# KMO_IO_MV6.net
KiCad netlist of a schematic drawn in EAGLE
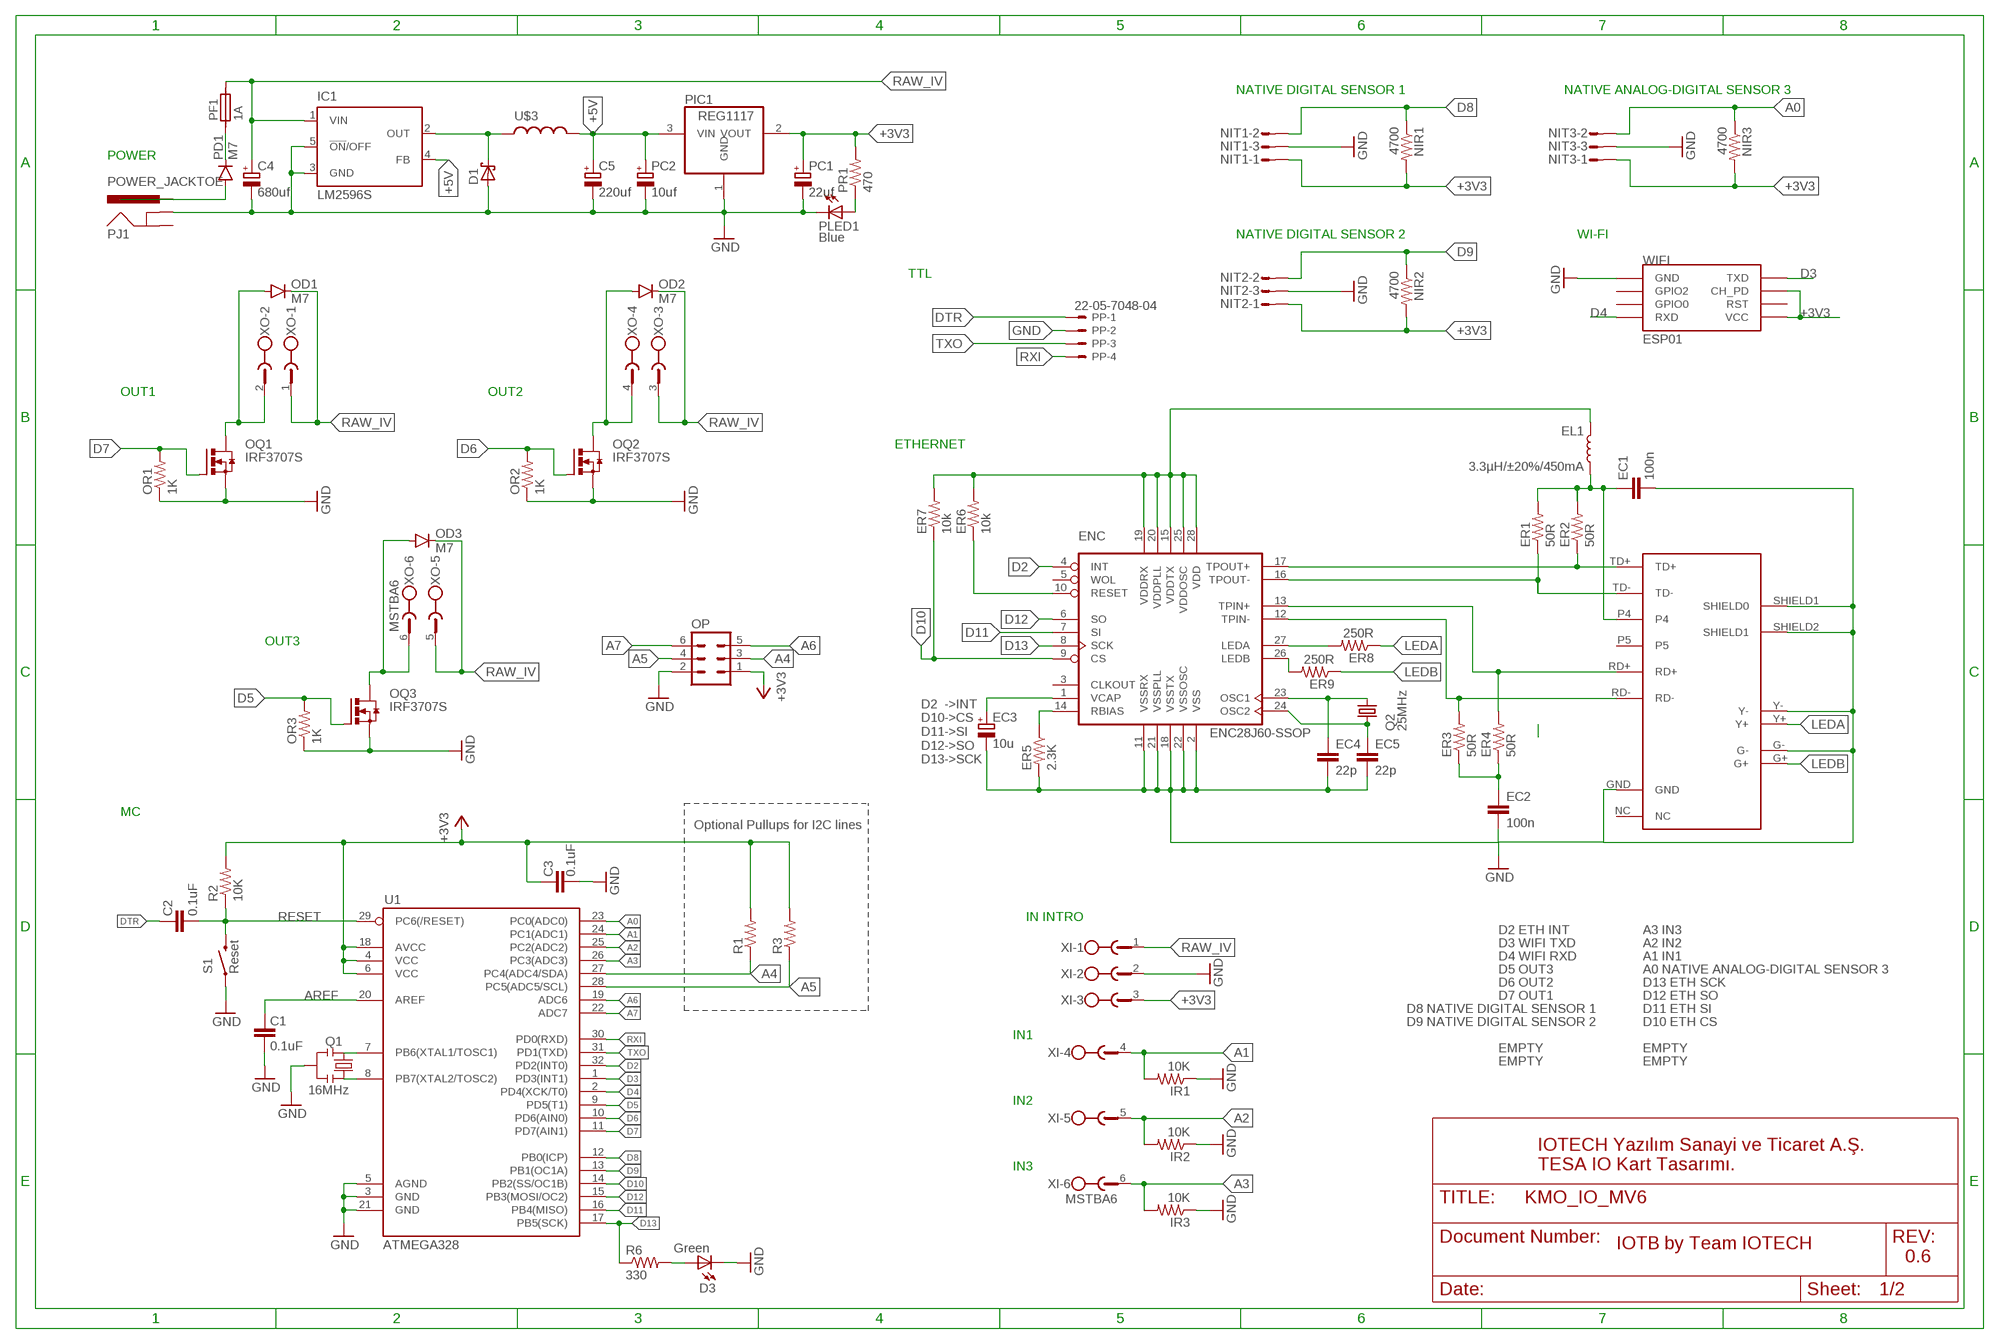
[diagram p0: schematic, sheet 1]
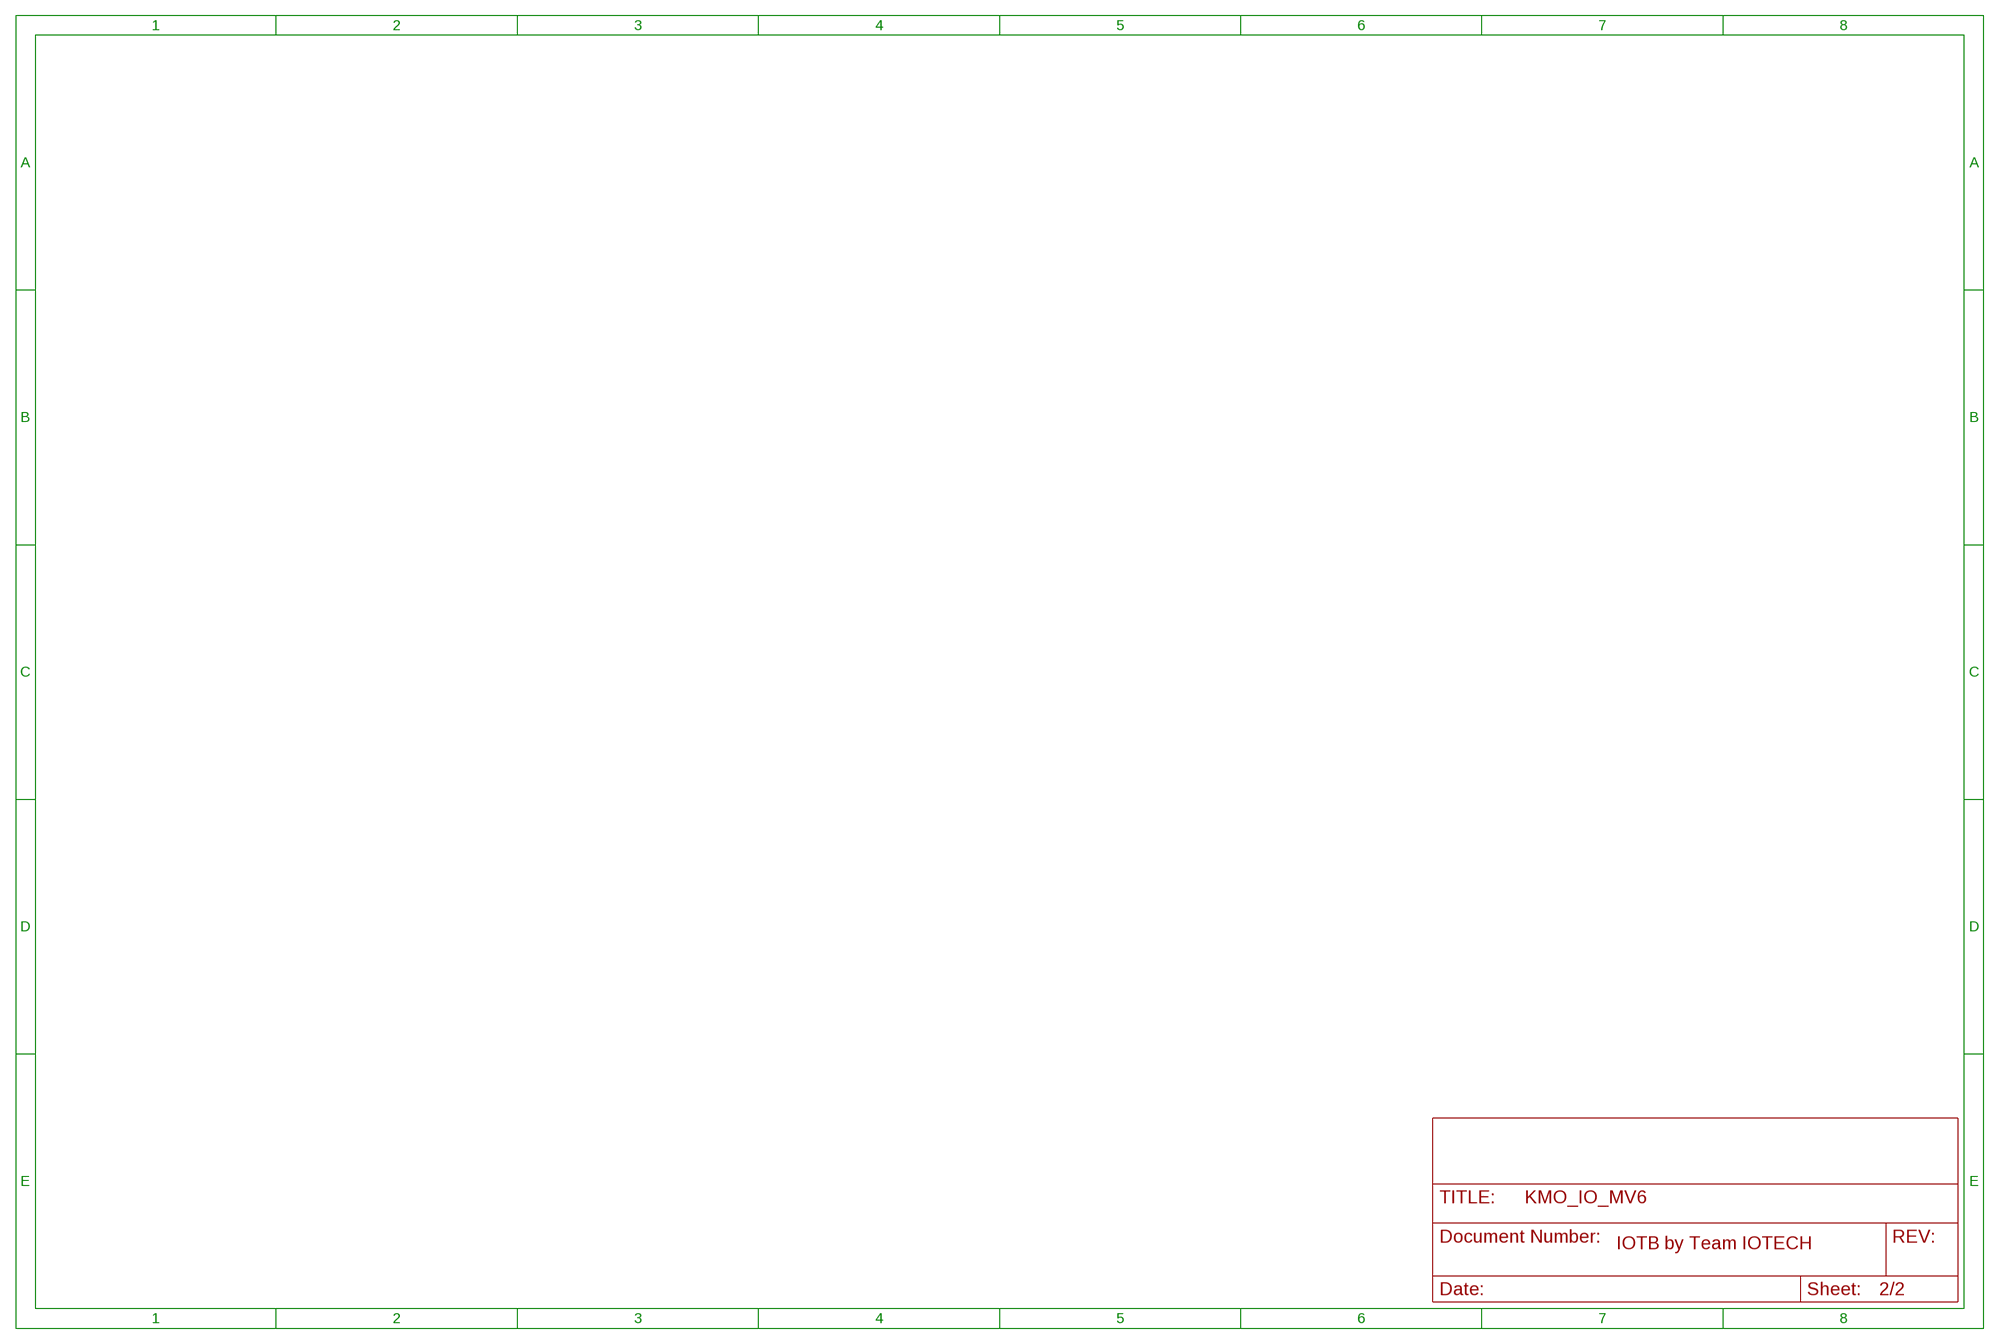
[diagram p1: schematic, sheet 2]

(export (version "E")
  (design (tool "Eeschema 10.0.6"))
  (components
    (comp (ref "C1")
      (value "0.1uF")
      (footprint "eagle-import:0805")
      (libsource (lib "eagle-import") (part "CAP0805"))
    )
    (comp (ref "C2")
      (value "0.1uF")
      (footprint "eagle-import:0805")
      (libsource (lib "eagle-import") (part "CAP0805"))
    )
    (comp (ref "C3")
      (value "0.1uF")
      (footprint "eagle-import:0805")
      (libsource (lib "eagle-import") (part "CAP0805"))
    )
    (comp (ref "C4")
      (value "680uf")
      (footprint "eagle-import:140CLH-1010")
      (libsource (lib "eagle-import") (part "CPOL-EU140CLH-1010"))
    )
    (comp (ref "C5")
      (value "220uf")
      (footprint "eagle-import:140CLH-1010")
      (libsource (lib "eagle-import") (part "CPOL-EU140CLH-1010"))
    )
    (comp (ref "D1")
      (value "SCHOTTKY-DIODESMD")
      (footprint "eagle-import:SMB")
      (libsource (lib "eagle-import") (part "SCHOTTKY-DIODESMD"))
    )
    (comp (ref "D3")
      (value "Green")
      (footprint "eagle-import:CHIP-LED0805")
      (libsource (lib "eagle-import") (part "LEDCHIP-LED0805"))
    )
    (comp (ref "EC1")
      (value "100n")
      (footprint "eagle-import:0805")
      (libsource (lib "eagle-import") (part "CAP0805"))
    )
    (comp (ref "EC2")
      (value "100n")
      (footprint "eagle-import:0805")
      (libsource (lib "eagle-import") (part "CAP0805"))
    )
    (comp (ref "EC3")
      (value "10u")
      (footprint "eagle-import:CT3216")
      (libsource (lib "eagle-import") (part "CPOL-EUCT3216"))
    )
    (comp (ref "EC4")
      (value "22p")
      (footprint "eagle-import:0805")
      (libsource (lib "eagle-import") (part "CAP0805"))
    )
    (comp (ref "EC5")
      (value "22p")
      (footprint "eagle-import:0805")
      (libsource (lib "eagle-import") (part "CAP0805"))
    )
    (comp (ref "EL1")
      (value "3.3µH/±20%/450mA")
      (footprint "eagle-import:0805")
      (libsource (lib "eagle-import") (part "INDUCTOR-0805-3.3UH"))
    )
    (comp (ref "ENC")
      (value "ENC28J60-SSOP")
      (footprint "eagle-import:SSOP28")
      (libsource (lib "eagle-import") (part "ENC28J60-SSOP"))
    )
    (comp (ref "ER1")
      (value "50R")
      (footprint "eagle-import:0805")
      (libsource (lib "eagle-import") (part "RESISTOR0805-RES"))
    )
    (comp (ref "ER2")
      (value "50R")
      (footprint "eagle-import:0805")
      (libsource (lib "eagle-import") (part "RESISTOR0805-RES"))
    )
    (comp (ref "ER3")
      (value "50R")
      (footprint "eagle-import:0805")
      (libsource (lib "eagle-import") (part "RESISTOR0805-RES"))
    )
    (comp (ref "ER4")
      (value "50R")
      (footprint "eagle-import:0805")
      (libsource (lib "eagle-import") (part "RESISTOR0805-RES"))
    )
    (comp (ref "ER5")
      (value "2.3K")
      (footprint "eagle-import:0805")
      (libsource (lib "eagle-import") (part "RESISTOR0805-RES"))
    )
    (comp (ref "ER6")
      (value "10k")
      (footprint "eagle-import:0805")
      (libsource (lib "eagle-import") (part "RESISTOR0805-RES"))
    )
    (comp (ref "ER7")
      (value "10k")
      (footprint "eagle-import:0805")
      (libsource (lib "eagle-import") (part "RESISTOR0805-RES"))
    )
    (comp (ref "ER8")
      (value "250R")
      (footprint "eagle-import:0805")
      (libsource (lib "eagle-import") (part "RESISTOR0805-RES"))
    )
    (comp (ref "ER9")
      (value "250R")
      (footprint "eagle-import:0805")
      (libsource (lib "eagle-import") (part "RESISTOR0805-RES"))
    )
    (comp (ref "IC1")
      (value "LM2596S")
      (footprint "eagle-import:TO263-5")
      (fields (field (name "MF") "NATIONAL SEMICONDUCTOR") (field (name "MPN") "LM2596S-ADJ/NOPB"))
      (libsource (lib "eagle-import") (part "LM2596S"))
    )
    (comp (ref "IR1")
      (value "10K")
      (footprint "eagle-import:0805")
      (libsource (lib "eagle-import") (part "RESISTOR0805-RES"))
    )
    (comp (ref "IR2")
      (value "10K")
      (footprint "eagle-import:0805")
      (libsource (lib "eagle-import") (part "RESISTOR0805-RES"))
    )
    (comp (ref "IR3")
      (value "10K")
      (footprint "eagle-import:0805")
      (libsource (lib "eagle-import") (part "RESISTOR0805-RES"))
    )
    (comp (ref "NIR1")
      (value "4700")
      (footprint "eagle-import:0805")
      (libsource (lib "eagle-import") (part "RESISTOR0805-RES"))
    )
    (comp (ref "NIR2")
      (value "4700")
      (footprint "eagle-import:0805")
      (libsource (lib "eagle-import") (part "RESISTOR0805-RES"))
    )
    (comp (ref "NIR3")
      (value "4700")
      (footprint "eagle-import:0805")
      (libsource (lib "eagle-import") (part "RESISTOR0805-RES"))
    )
    (comp (ref "NIT1")
      (value "S03P")
      (footprint "eagle-import:S03P")
      (libsource (lib "eagle-import") (part "S03P"))
    )
    (comp (ref "NIT2")
      (value "S03P")
      (footprint "eagle-import:S03P")
      (libsource (lib "eagle-import") (part "S03P"))
    )
    (comp (ref "NIT3")
      (value "S03P")
      (footprint "eagle-import:S03P")
      (libsource (lib "eagle-import") (part "S03P"))
    )
    (comp (ref "OD1")
      (value "M7")
      (footprint "eagle-import:SMA-DIODE")
      (libsource (lib "eagle-import") (part "DIODESMA"))
    )
    (comp (ref "OD2")
      (value "M7")
      (footprint "eagle-import:SMA-DIODE")
      (libsource (lib "eagle-import") (part "DIODESMA"))
    )
    (comp (ref "OD3")
      (value "M7")
      (footprint "eagle-import:SMA-DIODE")
      (libsource (lib "eagle-import") (part "DIODESMA"))
    )
    (comp (ref "OP")
      (value "MA03-2")
      (footprint "eagle-import:MA03-2")
      (libsource (lib "eagle-import") (part "MA03-2"))
    )
    (comp (ref "OQ1")
      (value "IRF3707S")
      (footprint "eagle-import:D2PACK")
      (libsource (lib "eagle-import") (part "IRF3704S"))
    )
    (comp (ref "OQ2")
      (value "IRF3707S")
      (footprint "eagle-import:D2PACK")
      (libsource (lib "eagle-import") (part "IRF3704S"))
    )
    (comp (ref "OQ3")
      (value "IRF3707S")
      (footprint "eagle-import:D2PACK")
      (libsource (lib "eagle-import") (part "IRF3704S"))
    )
    (comp (ref "OR1")
      (value "1K")
      (footprint "eagle-import:0805")
      (libsource (lib "eagle-import") (part "RESISTOR0805-RES"))
    )
    (comp (ref "OR2")
      (value "1K")
      (footprint "eagle-import:0805")
      (libsource (lib "eagle-import") (part "RESISTOR0805-RES"))
    )
    (comp (ref "OR3")
      (value "1K")
      (footprint "eagle-import:0805")
      (libsource (lib "eagle-import") (part "RESISTOR0805-RES"))
    )
    (comp (ref "PC1")
      (value "22uf")
      (footprint "eagle-import:CT3216")
      (libsource (lib "eagle-import") (part "CPOL-EUCT3216"))
    )
    (comp (ref "PC2")
      (value "10uf")
      (footprint "eagle-import:CT3216")
      (libsource (lib "eagle-import") (part "CPOL-EUCT3216"))
    )
    (comp (ref "PD1")
      (value "M7")
      (footprint "eagle-import:SMA-DIODE")
      (libsource (lib "eagle-import") (part "DIODESMA"))
    )
    (comp (ref "PF1")
      (value "1A")
      (footprint "eagle-import:1820")
      (libsource (lib "eagle-import") (part "SIBA194600"))
    )
    (comp (ref "PIC1")
      (value "REG1117")
      (footprint "eagle-import:SOT223")
      (libsource (lib "eagle-import") (part "REG1117"))
    )
    (comp (ref "PJ1")
      (value "POWER_JACKTOE")
      (footprint "eagle-import:POWER_JACK_SMD_OVERPASTE_TOE")
      (libsource (lib "eagle-import") (part "POWER_JACKTOE"))
    )
    (comp (ref "PLED1")
      (value "Blue")
      (footprint "eagle-import:CHIP-LED0805")
      (libsource (lib "eagle-import") (part "LEDCHIP-LED0805"))
    )
    (comp (ref "PP")
      (value "22-05-7048-04")
      (footprint "eagle-import:7395-04")
      (fields (field (name "MF") "MOLEX"))
      (libsource (lib "eagle-import") (part "22-?-0405-7048"))
    )
    (comp (ref "PR1")
      (value "470")
      (footprint "eagle-import:0805")
      (libsource (lib "eagle-import") (part "RESISTOR0805-RES"))
    )
    (comp (ref "Q1")
      (value "16MHz")
      (footprint "eagle-import:RESONATOR-SMD-1_1")
      (libsource (lib "eagle-import") (part "RESONATOR1{colon}1"))
    )
    (comp (ref "Q2")
      (value "25MHz")
      (footprint "eagle-import:5.0X3.2_2")
      (libsource (lib "eagle-import") (part "KX-9B"))
    )
    (comp (ref "R1")
      (value "RESISTOR0805-RES")
      (footprint "eagle-import:0805")
      (libsource (lib "eagle-import") (part "RESISTOR0805-RES"))
    )
    (comp (ref "R2")
      (value "10K")
      (footprint "eagle-import:0805")
      (libsource (lib "eagle-import") (part "RESISTOR0805-RES"))
    )
    (comp (ref "R3")
      (value "RESISTOR0805-RES")
      (footprint "eagle-import:0805")
      (libsource (lib "eagle-import") (part "RESISTOR0805-RES"))
    )
    (comp (ref "R6")
      (value "330")
      (footprint "eagle-import:0805")
      (libsource (lib "eagle-import") (part "RESISTOR0805-RES"))
    )
    (comp (ref "S1")
      (value "Reset")
      (footprint "eagle-import:TACTILE-SWITCH-SMD-ALT01")
      (libsource (lib "eagle-import") (part "SWITCH-MOMENTARY-2SMD-ALT01"))
    )
    (comp (ref "U$2")
      (value "HR911105A")
      (footprint "eagle-import:RJ45")
      (libsource (lib "eagle-import") (part "HR911105A"))
    )
    (comp (ref "U$3")
      (value "MSS1260")
      (footprint "eagle-import:MSS1260")
      (libsource (lib "eagle-import") (part "MSS1260"))
    )
    (comp (ref "U1")
      (value "ATMEGA328")
      (footprint "eagle-import:TQFP32-08")
      (libsource (lib "eagle-import") (part "ATMEGA168"))
    )
    (comp (ref "WIFI")
      (value "ESP01")
      (footprint "eagle-import:ESP01")
      (libsource (lib "eagle-import") (part "ESP01"))
    )
    (comp (ref "XI")
      (value "MSTBA6")
      (footprint "eagle-import:MSTBA6")
      (fields (field (name "MF") "FARNELL") (field (name "MPN") "1757284"))
      (libsource (lib "eagle-import") (part "MSTBA6"))
    )
    (comp (ref "XO")
      (value "MSTBA6")
      (footprint "eagle-import:MSTBA6")
      (fields (field (name "MF") "FARNELL") (field (name "MPN") "1757284"))
      (libsource (lib "eagle-import") (part "MSTBA6"))
    )
  )
  (nets
    (net (code "1") (name "+3V3") (class "Default")
      (node (ref "C3") (pin "2") (pinfunction "2_2") (pintype "passive"))
      (node (ref "EL1") (pin "1") (pinfunction "1_1") (pintype "passive"))
      (node (ref "ENC") (pin "15") (pinfunction "VDDTX_15") (pintype "power_in"))
      (node (ref "ENC") (pin "19") (pinfunction "VDDRX_19") (pintype "power_in"))
      (node (ref "ENC") (pin "20") (pinfunction "VDDPLL_20") (pintype "power_in"))
      (node (ref "ENC") (pin "25") (pinfunction "VDDOSC_25") (pintype "power_in"))
      (node (ref "ENC") (pin "28") (pinfunction "VDD_28") (pintype "power_in"))
      (node (ref "ER6") (pin "2") (pinfunction "2_2") (pintype "passive"))
      (node (ref "ER7") (pin "2") (pinfunction "2_2") (pintype "passive"))
      (node (ref "NIR1") (pin "2") (pinfunction "2_2") (pintype "passive"))
      (node (ref "NIR2") (pin "2") (pinfunction "2_2") (pintype "passive"))
      (node (ref "NIR3") (pin "2") (pinfunction "2_2") (pintype "passive"))
      (node (ref "NIT1") (pin "1") (pinfunction "S_1") (pintype "passive"))
      (node (ref "NIT2") (pin "1") (pinfunction "S_1") (pintype "passive"))
      (node (ref "NIT3") (pin "1") (pinfunction "S_1") (pintype "passive"))
      (node (ref "OP") (pin "1") (pinfunction "1_1") (pintype "passive"))
      (node (ref "PC1") (pin "+") (pinfunction "+_+") (pintype "passive"))
      (node (ref "PIC1") (pin "2") (pinfunction "VOUT_2") (pintype "output"))
      (node (ref "PR1") (pin "2") (pinfunction "2_2") (pintype "passive"))
      (node (ref "R1") (pin "2") (pinfunction "2_2") (pintype "passive"))
      (node (ref "R2") (pin "2") (pinfunction "2_2") (pintype "passive"))
      (node (ref "R3") (pin "2") (pinfunction "2_2") (pintype "passive"))
      (node (ref "U1") (pin "18") (pinfunction "AVCC_18") (pintype "bidirectional"))
      (node (ref "U1") (pin "4") (pinfunction "VCC_4") (pintype "bidirectional"))
      (node (ref "U1") (pin "6") (pinfunction "VCC_6") (pintype "bidirectional"))
      (node (ref "WIFI") (pin "CH_PD") (pinfunction "CH_PD_CH_PD") (pintype "bidirectional"))
      (node (ref "WIFI") (pin "VCC") (pinfunction "VCC_VCC") (pintype "bidirectional"))
      (node (ref "XI") (pin "3") (pinfunction "1_3") (pintype "passive"))
    )
    (net (code "2") (name "+5V") (class "Default")
      (node (ref "C5") (pin "+") (pinfunction "+_+") (pintype "passive"))
      (node (ref "IC1") (pin "4") (pinfunction "FB_4") (pintype "input"))
      (node (ref "PC2") (pin "+") (pinfunction "+_+") (pintype "passive"))
      (node (ref "PIC1") (pin "3") (pinfunction "VIN_3") (pintype "input"))
      (node (ref "U$3") (pin "P$1") (pinfunction "P$1_P$1") (pintype "passive"))
    )
    (net (code "3") (name "A0") (class "Default")
      (node (ref "NIR3") (pin "1") (pinfunction "1_1") (pintype "passive"))
      (node (ref "NIT3") (pin "2") (pinfunction "S_2") (pintype "passive"))
      (node (ref "U1") (pin "23") (pinfunction "PC0(ADC0)_23") (pintype "bidirectional"))
    )
    (net (code "4") (name "A1") (class "Default")
      (node (ref "IR1") (pin "2") (pinfunction "2_2") (pintype "passive"))
      (node (ref "U1") (pin "24") (pinfunction "PC1(ADC1)_24") (pintype "bidirectional"))
      (node (ref "XI") (pin "4") (pinfunction "1_4") (pintype "passive"))
    )
    (net (code "5") (name "A2") (class "Default")
      (node (ref "IR2") (pin "2") (pinfunction "2_2") (pintype "passive"))
      (node (ref "U1") (pin "25") (pinfunction "PC2(ADC2)_25") (pintype "bidirectional"))
      (node (ref "XI") (pin "5") (pinfunction "1_5") (pintype "passive"))
    )
    (net (code "6") (name "A3") (class "Default")
      (node (ref "IR3") (pin "2") (pinfunction "2_2") (pintype "passive"))
      (node (ref "U1") (pin "26") (pinfunction "PC3(ADC3)_26") (pintype "bidirectional"))
      (node (ref "XI") (pin "6") (pinfunction "1_6") (pintype "passive"))
    )
    (net (code "7") (name "A4") (class "Default")
      (node (ref "OP") (pin "3") (pinfunction "3_3") (pintype "passive"))
      (node (ref "R1") (pin "1") (pinfunction "1_1") (pintype "passive"))
      (node (ref "U1") (pin "27") (pinfunction "PC4(ADC4/SDA)_27") (pintype "bidirectional"))
    )
    (net (code "8") (name "A5") (class "Default")
      (node (ref "OP") (pin "4") (pinfunction "4_4") (pintype "passive"))
      (node (ref "R3") (pin "1") (pinfunction "1_1") (pintype "passive"))
      (node (ref "U1") (pin "28") (pinfunction "PC5(ADC5/SCL)_28") (pintype "bidirectional"))
    )
    (net (code "9") (name "A6") (class "Default")
      (node (ref "OP") (pin "5") (pinfunction "5_5") (pintype "passive"))
      (node (ref "U1") (pin "19") (pinfunction "ADC6_19") (pintype "bidirectional"))
    )
    (net (code "10") (name "A7") (class "Default")
      (node (ref "OP") (pin "6") (pinfunction "6_6") (pintype "passive"))
      (node (ref "U1") (pin "22") (pinfunction "ADC7_22") (pintype "bidirectional"))
    )
    (net (code "11") (name "AREF") (class "Default")
      (node (ref "C1") (pin "2") (pinfunction "2_2") (pintype "passive"))
      (node (ref "U1") (pin "20") (pinfunction "AREF_20") (pintype "bidirectional"))
    )
    (net (code "12") (name "D2") (class "Default")
      (node (ref "ENC") (pin "4") (pinfunction "INT_4") (pintype "output"))
      (node (ref "U1") (pin "32") (pinfunction "PD2(INT0)_32") (pintype "bidirectional"))
    )
    (net (code "13") (name "D3") (class "Default")
      (node (ref "U1") (pin "1") (pinfunction "PD3(INT1)_1") (pintype "bidirectional"))
      (node (ref "WIFI") (pin "TX") (pinfunction "TXD_TX") (pintype "bidirectional"))
    )
    (net (code "14") (name "D4") (class "Default")
      (node (ref "U1") (pin "2") (pinfunction "PD4(XCK/T0)_2") (pintype "bidirectional"))
      (node (ref "WIFI") (pin "RX") (pinfunction "RXD_RX") (pintype "bidirectional"))
    )
    (net (code "15") (name "D5") (class "Default")
      (node (ref "OQ3") (pin "1") (pinfunction "G_1") (pintype "passive"))
      (node (ref "OR3") (pin "2") (pinfunction "2_2") (pintype "passive"))
      (node (ref "U1") (pin "9") (pinfunction "PD5(T1)_9") (pintype "bidirectional"))
    )
    (net (code "16") (name "D6") (class "Default")
      (node (ref "OQ2") (pin "1") (pinfunction "G_1") (pintype "passive"))
      (node (ref "OR2") (pin "2") (pinfunction "2_2") (pintype "passive"))
      (node (ref "U1") (pin "10") (pinfunction "PD6(AIN0)_10") (pintype "bidirectional"))
    )
    (net (code "17") (name "D7") (class "Default")
      (node (ref "OQ1") (pin "1") (pinfunction "G_1") (pintype "passive"))
      (node (ref "OR1") (pin "2") (pinfunction "2_2") (pintype "passive"))
      (node (ref "U1") (pin "11") (pinfunction "PD7(AIN1)_11") (pintype "bidirectional"))
    )
    (net (code "18") (name "D8") (class "Default")
      (node (ref "NIR1") (pin "1") (pinfunction "1_1") (pintype "passive"))
      (node (ref "NIT1") (pin "2") (pinfunction "S_2") (pintype "passive"))
      (node (ref "U1") (pin "12") (pinfunction "PB0(ICP)_12") (pintype "bidirectional"))
    )
    (net (code "19") (name "D9") (class "Default")
      (node (ref "NIR2") (pin "1") (pinfunction "1_1") (pintype "passive"))
      (node (ref "NIT2") (pin "2") (pinfunction "S_2") (pintype "passive"))
      (node (ref "U1") (pin "13") (pinfunction "PB1(OC1A)_13") (pintype "bidirectional"))
    )
    (net (code "20") (name "D10") (class "Default")
      (node (ref "ENC") (pin "9") (pinfunction "CS_9") (pintype "input"))
      (node (ref "ER7") (pin "1") (pinfunction "1_1") (pintype "passive"))
      (node (ref "U1") (pin "14") (pinfunction "PB2(SS/OC1B)_14") (pintype "bidirectional"))
    )
    (net (code "21") (name "D11") (class "Default")
      (node (ref "ENC") (pin "7") (pinfunction "SI_7") (pintype "input"))
      (node (ref "U1") (pin "16") (pinfunction "PB4(MISO)_16") (pintype "bidirectional"))
    )
    (net (code "22") (name "D12") (class "Default")
      (node (ref "ENC") (pin "6") (pinfunction "SO_6") (pintype "output"))
      (node (ref "U1") (pin "15") (pinfunction "PB3(MOSI/OC2)_15") (pintype "bidirectional"))
    )
    (net (code "23") (name "D13") (class "Default")
      (node (ref "ENC") (pin "8") (pinfunction "SCK_8") (pintype "input"))
      (node (ref "R6") (pin "1") (pinfunction "1_1") (pintype "passive"))
      (node (ref "U1") (pin "17") (pinfunction "PB5(SCK)_17") (pintype "bidirectional"))
    )
    (net (code "24") (name "DTR") (class "Default")
      (node (ref "C2") (pin "2") (pinfunction "2_2") (pintype "passive"))
      (node (ref "PP") (pin "1") (pinfunction "S_1") (pintype "passive"))
    )
    (net (code "25") (name "GND") (class "Default")
      (node (ref "C1") (pin "1") (pinfunction "1_1") (pintype "passive"))
      (node (ref "C3") (pin "1") (pinfunction "1_1") (pintype "passive"))
      (node (ref "C4") (pin "-") (pinfunction "-_-") (pintype "passive"))
      (node (ref "C5") (pin "-") (pinfunction "-_-") (pintype "passive"))
      (node (ref "D1") (pin "A") (pinfunction "A_A") (pintype "passive"))
      (node (ref "D3") (pin "C") (pinfunction "C_C") (pintype "passive"))
      (node (ref "EC1") (pin "2") (pinfunction "2_2") (pintype "passive"))
      (node (ref "EC2") (pin "2") (pinfunction "2_2") (pintype "passive"))
      (node (ref "EC3") (pin "-") (pinfunction "-_-") (pintype "passive"))
      (node (ref "EC4") (pin "2") (pinfunction "2_2") (pintype "passive"))
      (node (ref "EC5") (pin "2") (pinfunction "2_2") (pintype "passive"))
      (node (ref "ENC") (pin "11") (pinfunction "VSSRX_11") (pintype "power_in"))
      (node (ref "ENC") (pin "18") (pinfunction "VSSTX_18") (pintype "power_in"))
      (node (ref "ENC") (pin "2") (pinfunction "VSS_2") (pintype "power_in"))
      (node (ref "ENC") (pin "21") (pinfunction "VSSPLL_21") (pintype "power_in"))
      (node (ref "ENC") (pin "22") (pinfunction "VSSOSC_22") (pintype "power_in"))
      (node (ref "ER5") (pin "2") (pinfunction "2_2") (pintype "passive"))
      (node (ref "IC1") (pin "3") (pinfunction "GND_3") (pintype "power_in"))
      (node (ref "IC1") (pin "5") (pinfunction "~{ON}/OFF_5") (pintype "input"))
      (node (ref "IR1") (pin "1") (pinfunction "1_1") (pintype "passive"))
      (node (ref "IR2") (pin "1") (pinfunction "1_1") (pintype "passive"))
      (node (ref "IR3") (pin "1") (pinfunction "1_1") (pintype "passive"))
      (node (ref "NIT1") (pin "3") (pinfunction "S_3") (pintype "passive"))
      (node (ref "NIT2") (pin "3") (pinfunction "S_3") (pintype "passive"))
      (node (ref "NIT3") (pin "3") (pinfunction "S_3") (pintype "passive"))
      (node (ref "OP") (pin "2") (pinfunction "2_2") (pintype "passive"))
      (node (ref "OQ1") (pin "3") (pinfunction "S_3") (pintype "passive"))
      (node (ref "OQ2") (pin "3") (pinfunction "S_3") (pintype "passive"))
      (node (ref "OQ3") (pin "3") (pinfunction "S_3") (pintype "passive"))
      (node (ref "OR1") (pin "1") (pinfunction "1_1") (pintype "passive"))
      (node (ref "OR2") (pin "1") (pinfunction "1_1") (pintype "passive"))
      (node (ref "OR3") (pin "1") (pinfunction "1_1") (pintype "passive"))
      (node (ref "PC1") (pin "-") (pinfunction "-_-") (pintype "passive"))
      (node (ref "PC2") (pin "-") (pinfunction "-_-") (pintype "passive"))
      (node (ref "PIC1") (pin "1") (pinfunction "GND_1") (pintype "power_in"))
      (node (ref "PJ1") (pin "GND") (pinfunction "GNDBREAK_GND") (pintype "bidirectional"))
      (node (ref "PLED1") (pin "C") (pinfunction "C_C") (pintype "passive"))
      (node (ref "PP") (pin "2") (pinfunction "S_2") (pintype "passive"))
      (node (ref "Q1") (pin "2") (pinfunction "2_2") (pintype "passive"))
      (node (ref "S1") (pin "1") (pinfunction "1_1") (pintype "passive"))
      (node (ref "S1") (pin "2") (pinfunction "1_2") (pintype "passive"))
      (node (ref "U$2") (pin "G-") (pinfunction "G-_G-") (pintype "bidirectional"))
      (node (ref "U$2") (pin "GND") (pinfunction "GND_GND") (pintype "bidirectional"))
      (node (ref "U$2") (pin "SHIELD1") (pinfunction "SHIELD0_SHIELD1") (pintype "bidirectional"))
      (node (ref "U$2") (pin "SHIELD2") (pinfunction "SHIELD1_SHIELD2") (pintype "bidirectional"))
      (node (ref "U$2") (pin "Y-") (pinfunction "Y-_Y-") (pintype "bidirectional"))
      (node (ref "U1") (pin "21") (pinfunction "GND_21") (pintype "bidirectional"))
      (node (ref "U1") (pin "3") (pinfunction "GND_3") (pintype "bidirectional"))
      (node (ref "U1") (pin "5") (pinfunction "AGND_5") (pintype "bidirectional"))
      (node (ref "WIFI") (pin "GND") (pinfunction "GND_GND") (pintype "bidirectional"))
      (node (ref "XI") (pin "2") (pinfunction "1_2") (pintype "passive"))
    )
    (net (code "26") (name "LEDA") (class "Default")
      (node (ref "ER8") (pin "1") (pinfunction "1_1") (pintype "passive"))
      (node (ref "U$2") (pin "Y+") (pinfunction "Y+_Y+") (pintype "bidirectional"))
    )
    (net (code "27") (name "LEDB") (class "Default")
      (node (ref "ER9") (pin "1") (pinfunction "1_1") (pintype "passive"))
      (node (ref "U$2") (pin "G+") (pinfunction "G+_G+") (pintype "bidirectional"))
    )
    (net (code "28") (name "Net-(D3-PadA)") (class "Default")
      (node (ref "D3") (pin "A") (pinfunction "A_A") (pintype "passive"))
      (node (ref "R6") (pin "2") (pinfunction "2_2") (pintype "passive"))
    )
    (net (code "29") (name "Net-(EC1-Pad1)") (class "Default")
      (node (ref "EC1") (pin "1") (pinfunction "1_1") (pintype "passive"))
      (node (ref "EL1") (pin "2") (pinfunction "2_2") (pintype "passive"))
      (node (ref "ER1") (pin "2") (pinfunction "2_2") (pintype "passive"))
      (node (ref "ER2") (pin "2") (pinfunction "2_2") (pintype "passive"))
      (node (ref "U$2") (pin "P4") (pinfunction "P4_P4") (pintype "bidirectional"))
    )
    (net (code "30") (name "Net-(EC2-Pad1)") (class "Default")
      (node (ref "EC2") (pin "1") (pinfunction "1_1") (pintype "passive"))
      (node (ref "ER3") (pin "1") (pinfunction "1_1") (pintype "passive"))
      (node (ref "ER4") (pin "1") (pinfunction "1_1") (pintype "passive"))
    )
    (net (code "31") (name "Net-(ENC-LEDA)") (class "Default")
      (node (ref "ENC") (pin "27") (pinfunction "LEDA_27") (pintype "output"))
      (node (ref "ER8") (pin "2") (pinfunction "2_2") (pintype "passive"))
    )
    (net (code "32") (name "Net-(ENC-LEDB)") (class "Default")
      (node (ref "ENC") (pin "26") (pinfunction "LEDB_26") (pintype "output"))
      (node (ref "ER9") (pin "2") (pinfunction "2_2") (pintype "passive"))
    )
    (net (code "33") (name "Net-(ENC-OSC1)") (class "Default")
      (node (ref "EC4") (pin "1") (pinfunction "1_1") (pintype "passive"))
      (node (ref "ENC") (pin "23") (pinfunction "OSC1_23") (pintype "input"))
      (node (ref "Q2") (pin "2") (pinfunction "2_2") (pintype "passive"))
    )
    (net (code "34") (name "Net-(ENC-OSC2)") (class "Default")
      (node (ref "EC5") (pin "1") (pinfunction "1_1") (pintype "passive"))
      (node (ref "ENC") (pin "24") (pinfunction "OSC2_24") (pintype "output"))
      (node (ref "Q2") (pin "1") (pinfunction "1_1") (pintype "passive"))
    )
    (net (code "35") (name "Net-(ENC-RBIAS)") (class "Default")
      (node (ref "ENC") (pin "14") (pinfunction "RBIAS_14") (pintype "passive"))
      (node (ref "ER5") (pin "1") (pinfunction "1_1") (pintype "passive"))
    )
    (net (code "36") (name "Net-(ENC-RESET)") (class "Default")
      (node (ref "ENC") (pin "10") (pinfunction "RESET_10") (pintype "input"))
      (node (ref "ER6") (pin "1") (pinfunction "1_1") (pintype "passive"))
    )
    (net (code "37") (name "Net-(ENC-TPIN+)") (class "Default")
      (node (ref "ENC") (pin "13") (pinfunction "TPIN+_13") (pintype "input"))
      (node (ref "ER4") (pin "2") (pinfunction "2_2") (pintype "passive"))
      (node (ref "U$2") (pin "RD+") (pinfunction "RD+_RD+") (pintype "bidirectional"))
    )
    (net (code "38") (name "Net-(ENC-TPIN-)") (class "Default")
      (node (ref "ENC") (pin "12") (pinfunction "TPIN-_12") (pintype "input"))
      (node (ref "ER3") (pin "2") (pinfunction "2_2") (pintype "passive"))
      (node (ref "U$2") (pin "RD-") (pinfunction "RD-_RD-") (pintype "bidirectional"))
    )
    (net (code "39") (name "Net-(ENC-TPOUT+)") (class "Default")
      (node (ref "ENC") (pin "17") (pinfunction "TPOUT+_17") (pintype "output"))
      (node (ref "ER2") (pin "1") (pinfunction "1_1") (pintype "passive"))
      (node (ref "U$2") (pin "TD+") (pinfunction "TD+_TD+") (pintype "bidirectional"))
    )
    (net (code "40") (name "Net-(ENC-TPOUT-)") (class "Default")
      (node (ref "ENC") (pin "16") (pinfunction "TPOUT-_16") (pintype "output"))
      (node (ref "ER1") (pin "1") (pinfunction "1_1") (pintype "passive"))
      (node (ref "U$2") (pin "TD-") (pinfunction "TD-_TD-") (pintype "bidirectional"))
    )
    (net (code "41") (name "Net-(ENC-VCAP)") (class "Default")
      (node (ref "EC3") (pin "+") (pinfunction "+_+") (pintype "passive"))
      (node (ref "ENC") (pin "1") (pinfunction "VCAP_1") (pintype "power_in"))
    )
    (net (code "42") (name "Net-(IC1-OUT)") (class "Default")
      (node (ref "D1") (pin "C") (pinfunction "C_C") (pintype "passive"))
      (node (ref "IC1") (pin "2") (pinfunction "OUT_2") (pintype "output"))
      (node (ref "U$3") (pin "P$2") (pinfunction "P$2_P$2") (pintype "passive"))
    )
    (net (code "43") (name "Net-(OQ1-D)") (class "Default")
      (node (ref "OD1") (pin "A") (pinfunction "A_A") (pintype "passive"))
      (node (ref "OQ1") (pin "2") (pinfunction "D_2") (pintype "passive"))
      (node (ref "XO") (pin "2") (pinfunction "1_2") (pintype "passive"))
    )
    (net (code "44") (name "Net-(OQ2-D)") (class "Default")
      (node (ref "OD2") (pin "A") (pinfunction "A_A") (pintype "passive"))
      (node (ref "OQ2") (pin "2") (pinfunction "D_2") (pintype "passive"))
      (node (ref "XO") (pin "4") (pinfunction "1_4") (pintype "passive"))
    )
    (net (code "45") (name "Net-(OQ3-D)") (class "Default")
      (node (ref "OD3") (pin "A") (pinfunction "A_A") (pintype "passive"))
      (node (ref "OQ3") (pin "2") (pinfunction "D_2") (pintype "passive"))
      (node (ref "XO") (pin "6") (pinfunction "1_6") (pintype "passive"))
    )
    (net (code "46") (name "Net-(PD1-PadC)") (class "Default")
      (node (ref "PD1") (pin "C") (pinfunction "C_C") (pintype "passive"))
      (node (ref "PF1") (pin "1") (pinfunction "1_1") (pintype "passive"))
    )
    (net (code "47") (name "Net-(PJ1-PWR)") (class "Default")
      (node (ref "PD1") (pin "A") (pinfunction "A_A") (pintype "passive"))
      (node (ref "PJ1") (pin "VIN0") (pinfunction "PWR_VIN0") (pintype "bidirectional"))
    )
    (net (code "48") (name "Net-(PLED1-PadA)") (class "Default")
      (node (ref "PLED1") (pin "A") (pinfunction "A_A") (pintype "passive"))
      (node (ref "PR1") (pin "1") (pinfunction "1_1") (pintype "passive"))
    )
    (net (code "49") (name "Net-(U1-PB6(XTAL1{slash}TOSC1))") (class "Default")
      (node (ref "Q1") (pin "1") (pinfunction "1_1") (pintype "passive"))
      (node (ref "U1") (pin "7") (pinfunction "PB6(XTAL1/TOSC1)_7") (pintype "bidirectional"))
    )
    (net (code "50") (name "Net-(U1-PB7(XTAL2{slash}TOSC2))") (class "Default")
      (node (ref "Q1") (pin "3") (pinfunction "3_3") (pintype "passive"))
      (node (ref "U1") (pin "8") (pinfunction "PB7(XTAL2/TOSC2)_8") (pintype "bidirectional"))
    )
    (net (code "51") (name "RAW_IV") (class "Default")
      (node (ref "C4") (pin "+") (pinfunction "+_+") (pintype "passive"))
      (node (ref "IC1") (pin "1") (pinfunction "VIN_1") (pintype "input"))
      (node (ref "OD1") (pin "C") (pinfunction "C_C") (pintype "passive"))
      (node (ref "OD2") (pin "C") (pinfunction "C_C") (pintype "passive"))
      (node (ref "OD3") (pin "C") (pinfunction "C_C") (pintype "passive"))
      (node (ref "PF1") (pin "2") (pinfunction "2_2") (pintype "passive"))
      (node (ref "XI") (pin "1") (pinfunction "1_1") (pintype "passive"))
      (node (ref "XO") (pin "1") (pinfunction "1_1") (pintype "passive"))
      (node (ref "XO") (pin "3") (pinfunction "1_3") (pintype "passive"))
      (node (ref "XO") (pin "5") (pinfunction "1_5") (pintype "passive"))
    )
    (net (code "52") (name "RESET") (class "Default")
      (node (ref "C2") (pin "1") (pinfunction "1_1") (pintype "passive"))
      (node (ref "R2") (pin "1") (pinfunction "1_1") (pintype "passive"))
      (node (ref "S1") (pin "3") (pinfunction "2_3") (pintype "passive"))
      (node (ref "S1") (pin "4") (pinfunction "2_4") (pintype "passive"))
      (node (ref "U1") (pin "29") (pinfunction "PC6(/RESET)_29") (pintype "bidirectional"))
    )
    (net (code "53") (name "RXI") (class "Default")
      (node (ref "PP") (pin "4") (pinfunction "S_4") (pintype "passive"))
      (node (ref "U1") (pin "30") (pinfunction "PD0(RXD)_30") (pintype "bidirectional"))
    )
    (net (code "54") (name "TXO") (class "Default")
      (node (ref "PP") (pin "3") (pinfunction "S_3") (pintype "passive"))
      (node (ref "U1") (pin "31") (pinfunction "PD1(TXD)_31") (pintype "bidirectional"))
    )
    (net (code "55") (name "unconnected-(ENC-CLKOUT-Pad3)") (class "Default")
      (node (ref "ENC") (pin "3") (pinfunction "CLKOUT_3") (pintype "output"))
    )
    (net (code "56") (name "unconnected-(ENC-WOL-Pad5)") (class "Default")
      (node (ref "ENC") (pin "5") (pinfunction "WOL_5") (pintype "output"))
    )
    (net (code "57") (name "unconnected-(PJ1-GND-PadP$4)") (class "Default")
      (node (ref "PJ1") (pin "P$4") (pinfunction "GND_P$4") (pintype "bidirectional"))
    )
    (net (code "58") (name "unconnected-(U$2-PadNC)") (class "Default")
      (node (ref "U$2") (pin "NC") (pinfunction "NC_NC") (pintype "bidirectional"))
    )
    (net (code "59") (name "unconnected-(U$2-PadP5)") (class "Default")
      (node (ref "U$2") (pin "P5") (pinfunction "P5_P5") (pintype "bidirectional"))
    )
    (net (code "60") (name "unconnected-(WIFI-PadGPIO0)") (class "Default")
      (node (ref "WIFI") (pin "GPIO0") (pinfunction "GPIO0_GPIO0") (pintype "bidirectional"))
    )
    (net (code "61") (name "unconnected-(WIFI-PadGPIO2)") (class "Default")
      (node (ref "WIFI") (pin "GPIO2") (pinfunction "GPIO2_GPIO2") (pintype "bidirectional"))
    )
    (net (code "62") (name "unconnected-(WIFI-PadRST)") (class "Default")
      (node (ref "WIFI") (pin "RST") (pinfunction "RST_RST") (pintype "bidirectional"))
    )
  )
)
